# Sheet2.net
KiCad netlist of a schematic drawn in Altium Designer
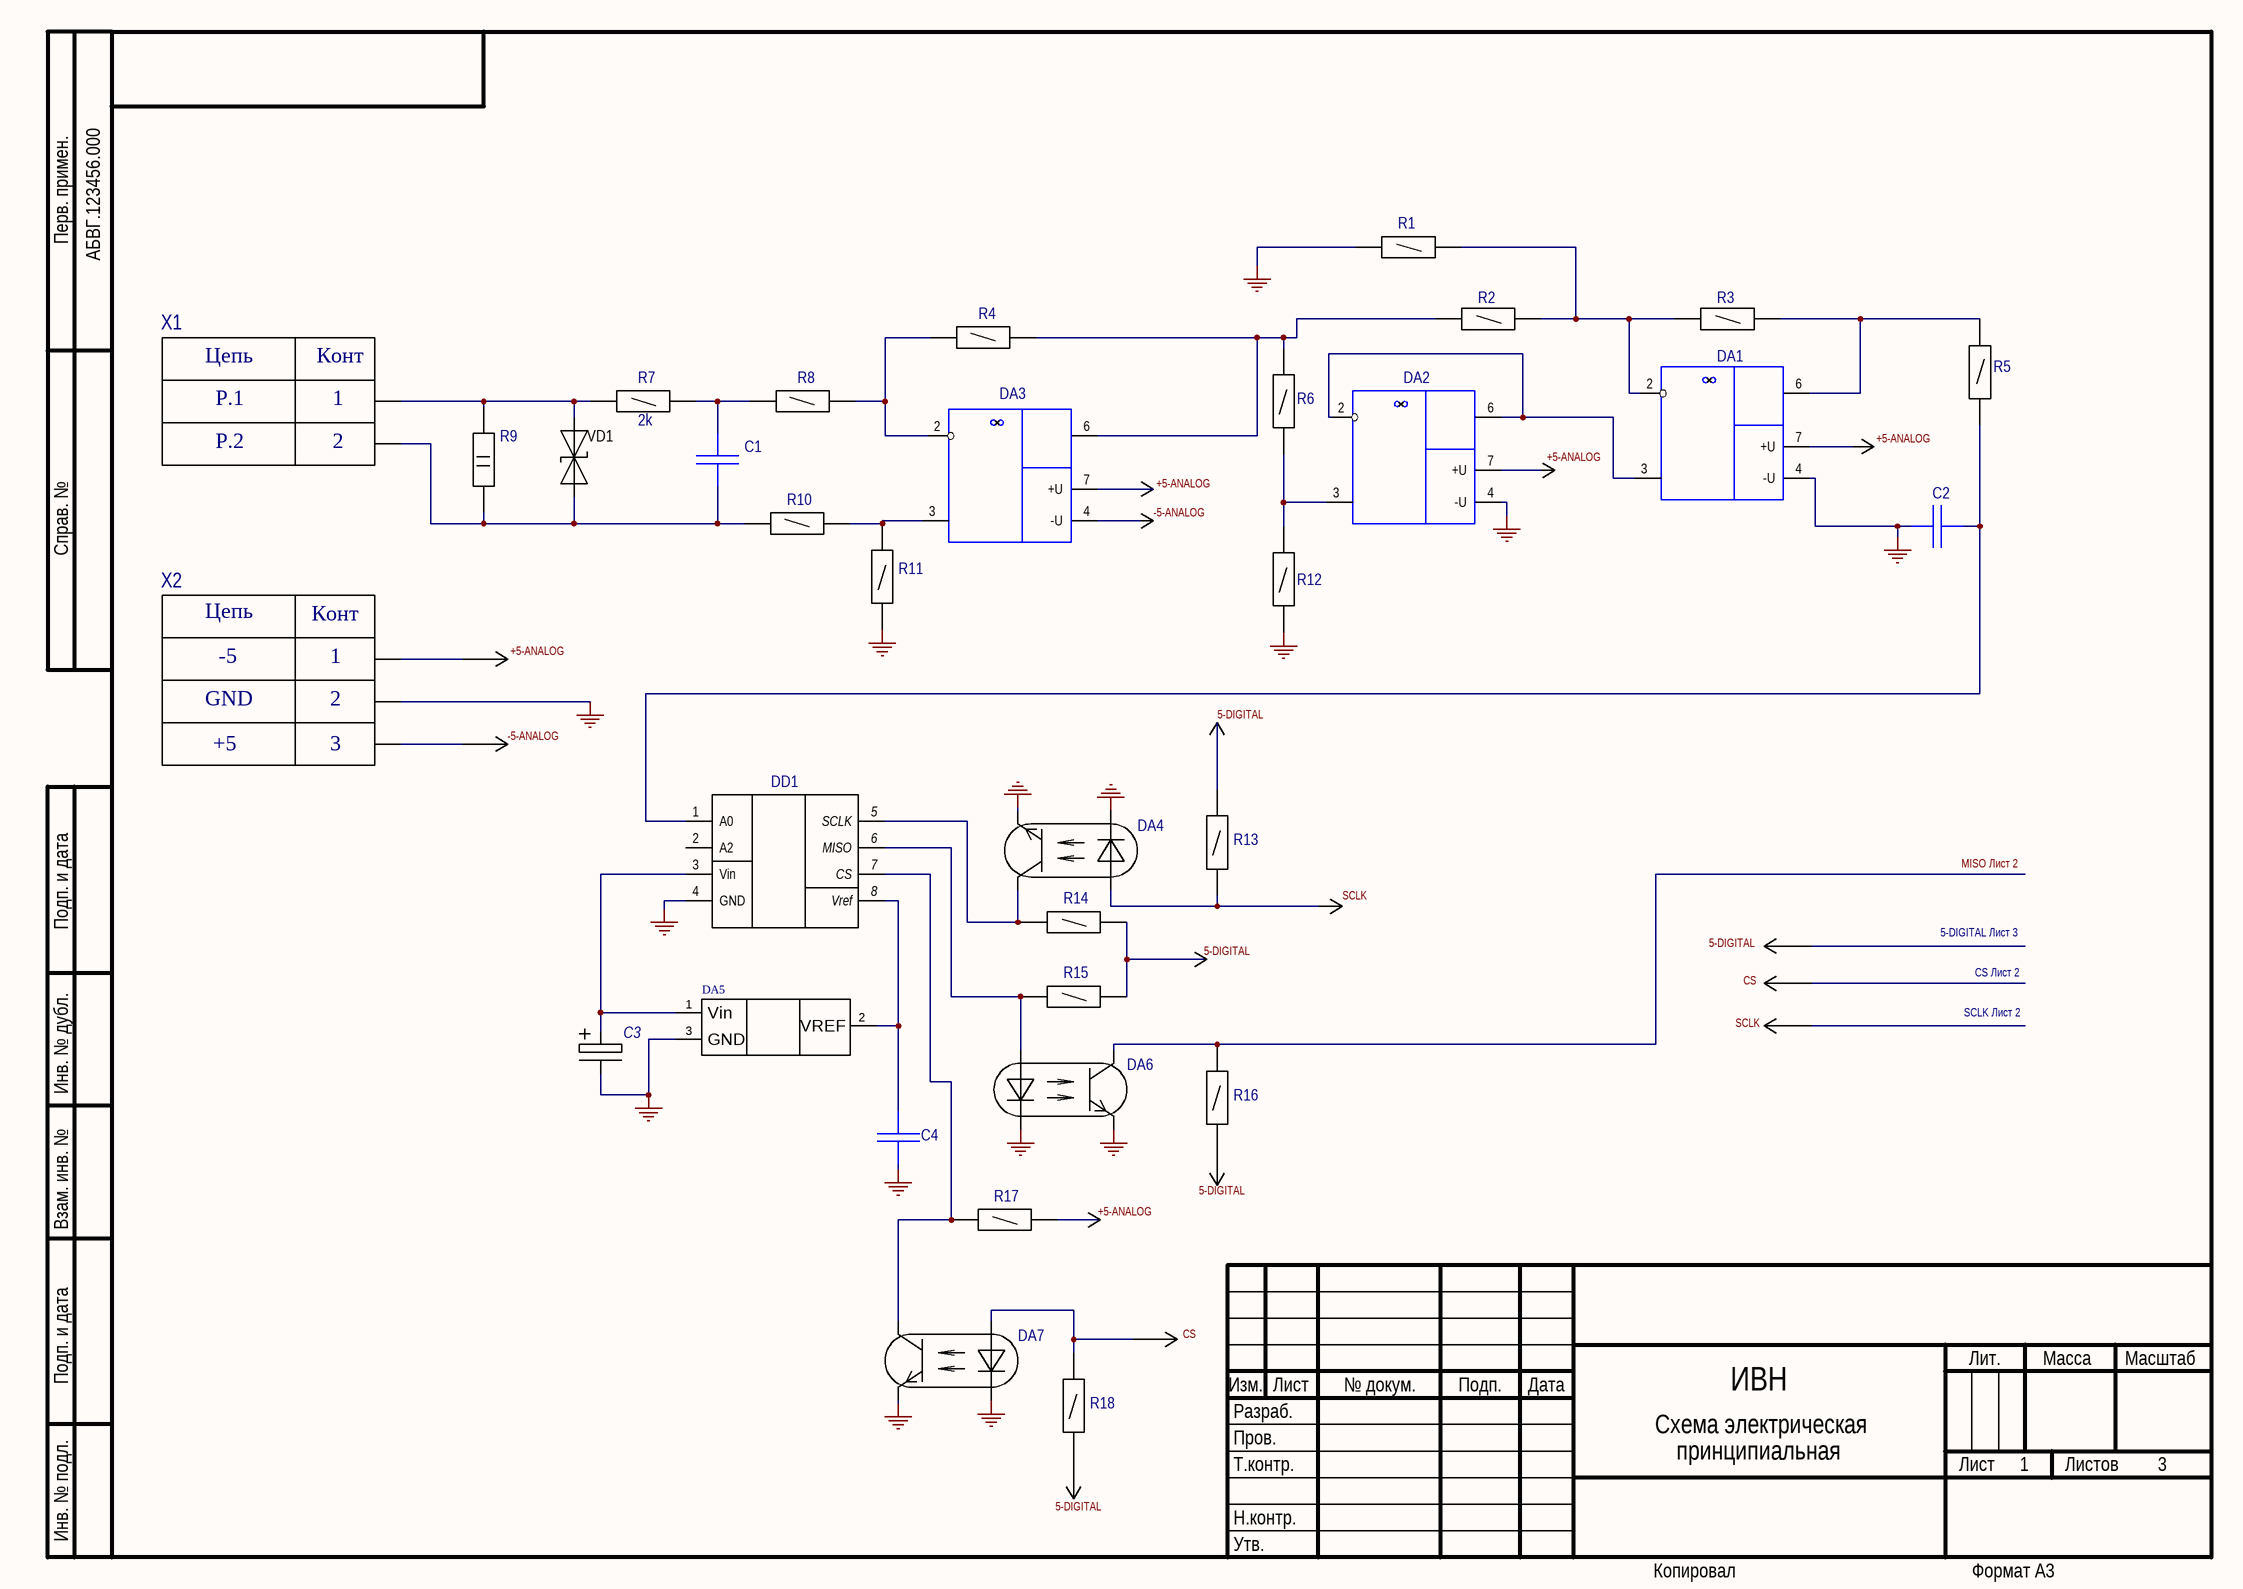
[diagram p0: Sheet2.SchDoc]

(export (version "E")
  (design (tool "Eeschema 10.0.6"))
  (components
    (comp (ref "C1") (value "470n") (footprint "CAP SMD 1206") (libsource (lib "Schlib1") (part "CAP")))
    (comp (ref "C2") (value "CAP") (footprint "CAP SMD 1812") (libsource (lib "Schlib1") (part "CAP")))
    (comp (ref "C3") (value "~") (footprint "Radial 5x11mm") (libsource (lib "Schlib1") (part "CapPol_1")))
    (comp (ref "C4") (value "CAP") (footprint "CAP SMD 1812") (libsource (lib "Schlib1") (part "CAP")))
    (comp (ref "DA1")
      (value "MCP601-I/SN")
      (footprint "MCP601-I/SN")
      (libsource (lib "Schlib1") (part "MCP601-I/SN"))
    )
    (comp (ref "DA2")
      (value "MCP601-I/SN")
      (footprint "MCP601-I/SN")
      (libsource (lib "Schlib1") (part "MCP601-I/SN"))
    )
    (comp (ref "DA3")
      (value "LT1816CS")
      (footprint "MCP601-I/SN")
      (libsource (lib "Schlib1") (part "LT1816CS"))
    )
    (comp (ref "DA4") (value "PC817") (footprint "DIP4") (libsource (lib "") (part "PC817_1")))
    (comp (ref "DA5") (value "MCP1541") (footprint "TO-92") (libsource (lib "Schlib1") (part "MCP1541")))
    (comp (ref "DA6") (value "PC817") (footprint "DIP4") (libsource (lib "") (part "PC817_1")))
    (comp (ref "DA7") (value "PC817") (footprint "DIP4") (libsource (lib "Schlib1") (part "PC817")))
    (comp (ref "DD1") (value "MCP3201") (footprint "MCP3201") (libsource (lib "Schlib1") (part "MCP3201")))
    (comp (ref "R1")
      (value "resistor")
      (footprint "Resistor SMD 1206")
      (libsource (lib "Schlib1") (part "resistor"))
    )
    (comp (ref "R2")
      (value "resistor")
      (footprint "Resistor SMD 1206")
      (libsource (lib "Schlib1") (part "resistor"))
    )
    (comp (ref "R3")
      (value "resistor")
      (footprint "Resistor SMD 1206")
      (libsource (lib "Schlib1") (part "resistor"))
    )
    (comp (ref "R4")
      (value "21k")
      (footprint "Resistor SMD 1206")
      (libsource (lib "Schlib1") (part "resistor"))
    )
    (comp (ref "R5")
      (value "resistor")
      (footprint "Resistor SMD 1206")
      (libsource (lib "Schlib1") (part "resistor"))
    )
    (comp (ref "R6")
      (value "resistor")
      (footprint "Resistor SMD 1206")
      (libsource (lib "Schlib1") (part "resistor"))
    )
    (comp (ref "R7")
      (value "2k")
      (footprint "RESISTOR SMD 0805")
      (libsource (lib "Schlib1") (part "resistor"))
    )
    (comp (ref "R8")
      (value "10k")
      (footprint "Resistor SMD 1206")
      (libsource (lib "Schlib1") (part "resistor"))
    )
    (comp (ref "R9")
      (value "230")
      (footprint "RESISTOR SMD 2512")
      (libsource (lib "Schlib1") (part "2W RES"))
    )
    (comp (ref "R10")
      (value "10k")
      (footprint "Resistor SMD 1206")
      (libsource (lib "Schlib1") (part "resistor"))
    )
    (comp (ref "R11")
      (value "resistor")
      (footprint "Resistor SMD 1206")
      (libsource (lib "Schlib1") (part "resistor"))
    )
    (comp (ref "R12")
      (value "resistor")
      (footprint "Resistor SMD 1206")
      (libsource (lib "Schlib1") (part "resistor"))
    )
    (comp (ref "R13")
      (value "resistor")
      (footprint "Resistor SMD 1206")
      (libsource (lib "Schlib1") (part "resistor"))
    )
    (comp (ref "R14")
      (value "resistor")
      (footprint "Resistor SMD 1206")
      (libsource (lib "Schlib1") (part "resistor"))
    )
    (comp (ref "R15")
      (value "resistor")
      (footprint "Resistor SMD 1206")
      (libsource (lib "Schlib1") (part "resistor"))
    )
    (comp (ref "R16")
      (value "resistor")
      (footprint "Resistor SMD 1206")
      (libsource (lib "Schlib1") (part "resistor"))
    )
    (comp (ref "R17")
      (value "resistor")
      (footprint "Resistor SMD 1206")
      (libsource (lib "Schlib1") (part "resistor"))
    )
    (comp (ref "R18")
      (value "resistor")
      (footprint "Resistor SMD 1206")
      (libsource (lib "Schlib1") (part "resistor"))
    )
    (comp (ref "VD1")
      (value "PESD5V0L1BA")
      (footprint "DIOM5226X230N")
      (libsource (lib "Schlib1") (part "VD_TVS"))
    )
    (comp (ref "X1")
      (value "connector_shunt")
      (footprint "PLS-02")
      (libsource (lib "Schlib1") (part "connector_shunt"))
    )
    (comp (ref "X2") (value "PLS3") (footprint "PLS-3") (libsource (lib "Schlib1") (part "PLS3")))
  )
  (nets
    (net (code "1") (name "/+5-ANALOG") (class "Default")
      (node (ref "R17") (pin "1") (pinfunction "1_1") (pintype "passive"))
    )
    (net (code "3") (name "/5-DIGITAL") (class "Default")
      (node (ref "R13") (pin "2") (pinfunction "2_2") (pintype "passive"))
      (node (ref "R14") (pin "1") (pinfunction "1_1") (pintype "passive"))
      (node (ref "R15") (pin "1") (pinfunction "1_1") (pintype "passive"))
    )
    (net (code "8") (name "GND") (class "Default")
      (node (ref "C2") (pin "1") (pinfunction "1_1") (pintype "passive"))
      (node (ref "C3") (pin "1") (pinfunction "1_1") (pintype "passive"))
      (node (ref "C4") (pin "1") (pinfunction "1_1") (pintype "passive"))
      (node (ref "DA1") (pin "4") (pinfunction "-U_4") (pintype "passive"))
      (node (ref "DA2") (pin "4") (pinfunction "-U_4") (pintype "passive"))
      (node (ref "DA4") (pin "2") (pinfunction "2_2") (pintype "passive"))
      (node (ref "DA4") (pin "3") (pinfunction "3_3") (pintype "passive"))
      (node (ref "DA5") (pin "3") (pinfunction "GND_3") (pintype "power_in"))
      (node (ref "DA6") (pin "2") (pinfunction "2_2") (pintype "passive"))
      (node (ref "DA6") (pin "3") (pinfunction "3_3") (pintype "passive"))
      (node (ref "DA7") (pin "2") (pinfunction "2_2") (pintype "passive"))
      (node (ref "DA7") (pin "3") (pinfunction "3_3") (pintype "passive"))
      (node (ref "DD1") (pin "4") (pinfunction "GND_4") (pintype "passive"))
      (node (ref "R1") (pin "2") (pinfunction "2_2") (pintype "passive"))
      (node (ref "R11") (pin "1") (pinfunction "1_1") (pintype "passive"))
      (node (ref "R12") (pin "1") (pinfunction "1_1") (pintype "passive"))
      (node (ref "X2") (pin "2") (pinfunction "2_2") (pintype "passive"))
    )
    (net (code "9") (name "Net-(C1-Pad1)") (class "Default")
      (node (ref "C1") (pin "1") (pinfunction "1_1") (pintype "passive"))
      (node (ref "R7") (pin "1") (pinfunction "1_1") (pintype "passive"))
      (node (ref "R8") (pin "1") (pinfunction "1_1") (pintype "passive"))
    )
    (net (code "10") (name "Net-(C1-Pad2)") (class "Default")
      (node (ref "C1") (pin "2") (pinfunction "2_2") (pintype "passive"))
      (node (ref "R10") (pin "1") (pinfunction "1_1") (pintype "passive"))
      (node (ref "R9") (pin "1") (pinfunction "1_1") (pintype "passive"))
      (node (ref "VD1") (pin "1") (pinfunction "1_1") (pintype "passive"))
      (node (ref "X1") (pin "1") (pinfunction "1_1") (pintype "passive"))
    )
    (net (code "11") (name "Net-(DA1-+(неинвентирующий))") (class "Default")
      (node (ref "DA1") (pin "3") (pinfunction "+(неинвентирующий)_3") (pintype "passive"))
      (node (ref "DA2") (pin "2") (pinfunction "-(инвентирующий)_2") (pintype "passive"))
      (node (ref "DA2") (pin "6") (pinfunction "X_6") (pintype "passive"))
    )
    (net (code "12") (name "Net-(DA1--(инвентирующий))") (class "Default")
      (node (ref "DA1") (pin "2") (pinfunction "-(инвентирующий)_2") (pintype "passive"))
      (node (ref "R1") (pin "1") (pinfunction "1_1") (pintype "passive"))
      (node (ref "R2") (pin "1") (pinfunction "1_1") (pintype "passive"))
      (node (ref "R3") (pin "2") (pinfunction "2_2") (pintype "passive"))
    )
    (net (code "13") (name "Net-(DA1-X)") (class "Default")
      (node (ref "DA1") (pin "6") (pinfunction "X_6") (pintype "passive"))
      (node (ref "R3") (pin "1") (pinfunction "1_1") (pintype "passive"))
      (node (ref "R5") (pin "1") (pinfunction "1_1") (pintype "passive"))
    )
    (net (code "14") (name "Net-(DA2-+(неинвентирующий))") (class "Default")
      (node (ref "DA2") (pin "3") (pinfunction "+(неинвентирующий)_3") (pintype "passive"))
      (node (ref "R12") (pin "2") (pinfunction "2_2") (pintype "passive"))
      (node (ref "R6") (pin "1") (pinfunction "1_1") (pintype "passive"))
    )
    (net (code "15") (name "Net-(DA3-+(неинвентирующий))") (class "Default")
      (node (ref "DA3") (pin "3") (pinfunction "+(неинвентирующий)_3") (pintype "passive"))
      (node (ref "R10") (pin "2") (pinfunction "2_2") (pintype "passive"))
      (node (ref "R11") (pin "2") (pinfunction "2_2") (pintype "passive"))
    )
    (net (code "16") (name "Net-(DA3--(инвентирующий))") (class "Default")
      (node (ref "DA3") (pin "2") (pinfunction "-(инвентирующий)_2") (pintype "passive"))
      (node (ref "R4") (pin "1") (pinfunction "1_1") (pintype "passive"))
      (node (ref "R8") (pin "2") (pinfunction "2_2") (pintype "passive"))
    )
    (net (code "17") (name "Net-(DA3-X)") (class "Default")
      (node (ref "DA3") (pin "6") (pinfunction "X_6") (pintype "passive"))
      (node (ref "R2") (pin "2") (pinfunction "2_2") (pintype "passive"))
      (node (ref "R4") (pin "2") (pinfunction "2_2") (pintype "passive"))
      (node (ref "R6") (pin "2") (pinfunction "2_2") (pintype "passive"))
    )
    (net (code "18") (name "Net-(DA4-Pad1)") (class "Default")
      (node (ref "DA4") (pin "1") (pinfunction "1_1") (pintype "passive"))
      (node (ref "R13") (pin "1") (pinfunction "1_1") (pintype "passive"))
    )
    (net (code "19") (name "Net-(DA5-VREF)") (class "Default")
      (node (ref "C4") (pin "2") (pinfunction "2_2") (pintype "passive"))
      (node (ref "DA5") (pin "2") (pinfunction "VREF_2") (pintype "power_in"))
      (node (ref "DD1") (pin "8") (pinfunction "Vref_8") (pintype "passive"))
    )
    (net (code "20") (name "Net-(DA5-Vin)") (class "Default")
      (node (ref "C3") (pin "2") (pinfunction "2_2") (pintype "passive"))
      (node (ref "DA5") (pin "1") (pinfunction "Vin_1") (pintype "power_in"))
      (node (ref "DD1") (pin "3") (pinfunction "Vin_3") (pintype "passive"))
    )
    (net (code "21") (name "Net-(DA6-Pad4)") (class "Default")
      (node (ref "DA6") (pin "4") (pinfunction "4_4") (pintype "passive"))
      (node (ref "R16") (pin "2") (pinfunction "2_2") (pintype "passive"))
    )
    (net (code "22") (name "Net-(DA7-Pad1)") (class "Default")
      (node (ref "DA7") (pin "1") (pinfunction "1_1") (pintype "passive"))
      (node (ref "R18") (pin "2") (pinfunction "2_2") (pintype "passive"))
    )
    (net (code "23") (name "Net-(DD1-A0)") (class "Default")
      (node (ref "C2") (pin "2") (pinfunction "2_2") (pintype "passive"))
      (node (ref "DD1") (pin "1") (pinfunction "A0_1") (pintype "passive"))
      (node (ref "R5") (pin "2") (pinfunction "2_2") (pintype "passive"))
    )
    (net (code "24") (name "Net-(DD1-CS)") (class "Default")
      (node (ref "DA7") (pin "4") (pinfunction "4_4") (pintype "passive"))
      (node (ref "DD1") (pin "7") (pinfunction "CS_7") (pintype "passive"))
      (node (ref "R17") (pin "2") (pinfunction "2_2") (pintype "passive"))
    )
    (net (code "25") (name "Net-(DD1-MISO)") (class "Default")
      (node (ref "DA6") (pin "1") (pinfunction "1_1") (pintype "passive"))
      (node (ref "DD1") (pin "6") (pinfunction "MISO_6") (pintype "passive"))
      (node (ref "R15") (pin "2") (pinfunction "2_2") (pintype "passive"))
    )
    (net (code "26") (name "Net-(DD1-SCLK)") (class "Default")
      (node (ref "DA4") (pin "4") (pinfunction "4_4") (pintype "passive"))
      (node (ref "DD1") (pin "5") (pinfunction "SCLK_5") (pintype "passive"))
      (node (ref "R14") (pin "2") (pinfunction "2_2") (pintype "passive"))
    )
    (net (code "27") (name "Net-(R7-Pad2)") (class "Default")
      (node (ref "R7") (pin "2") (pinfunction "2_2") (pintype "passive"))
      (node (ref "R9") (pin "2") (pinfunction "2_2") (pintype "passive"))
      (node (ref "VD1") (pin "2") (pinfunction "2_2") (pintype "passive"))
      (node (ref "X1") (pin "2") (pinfunction "2_2") (pintype "passive"))
    )
    (net (code "28") (name "unconnected-(DA1-+U-Pad7)") (class "Default")
      (node (ref "DA1") (pin "7") (pinfunction "+U_7") (pintype "passive"))
    )
    (net (code "29") (name "unconnected-(DA2-+U-Pad7)") (class "Default")
      (node (ref "DA2") (pin "7") (pinfunction "+U_7") (pintype "passive"))
    )
    (net (code "30") (name "unconnected-(DA3-+U-Pad7)") (class "Default")
      (node (ref "DA3") (pin "7") (pinfunction "+U_7") (pintype "passive"))
    )
    (net (code "31") (name "unconnected-(DA3--U-Pad4)") (class "Default")
      (node (ref "DA3") (pin "4") (pinfunction "-U_4") (pintype "passive"))
    )
    (net (code "32") (name "unconnected-(DD1-A2-Pad2)") (class "Default")
      (node (ref "DD1") (pin "2") (pinfunction "A2_2") (pintype "passive"))
    )
    (net (code "33") (name "unconnected-(R16-Pad1)") (class "Default")
      (node (ref "R16") (pin "1") (pinfunction "1_1") (pintype "passive"))
    )
    (net (code "34") (name "unconnected-(R18-Pad1)") (class "Default")
      (node (ref "R18") (pin "1") (pinfunction "1_1") (pintype "passive"))
    )
    (net (code "35") (name "unconnected-(X2-Pad1)") (class "Default")
      (node (ref "X2") (pin "1") (pinfunction "1_1") (pintype "passive"))
    )
    (net (code "36") (name "unconnected-(X2-Pad3)") (class "Default")
      (node (ref "X2") (pin "3") (pinfunction "3_3") (pintype "passive"))
    )
  )
)
